# CREMA.net
KiCad netlist of a schematic drawn in EAGLE
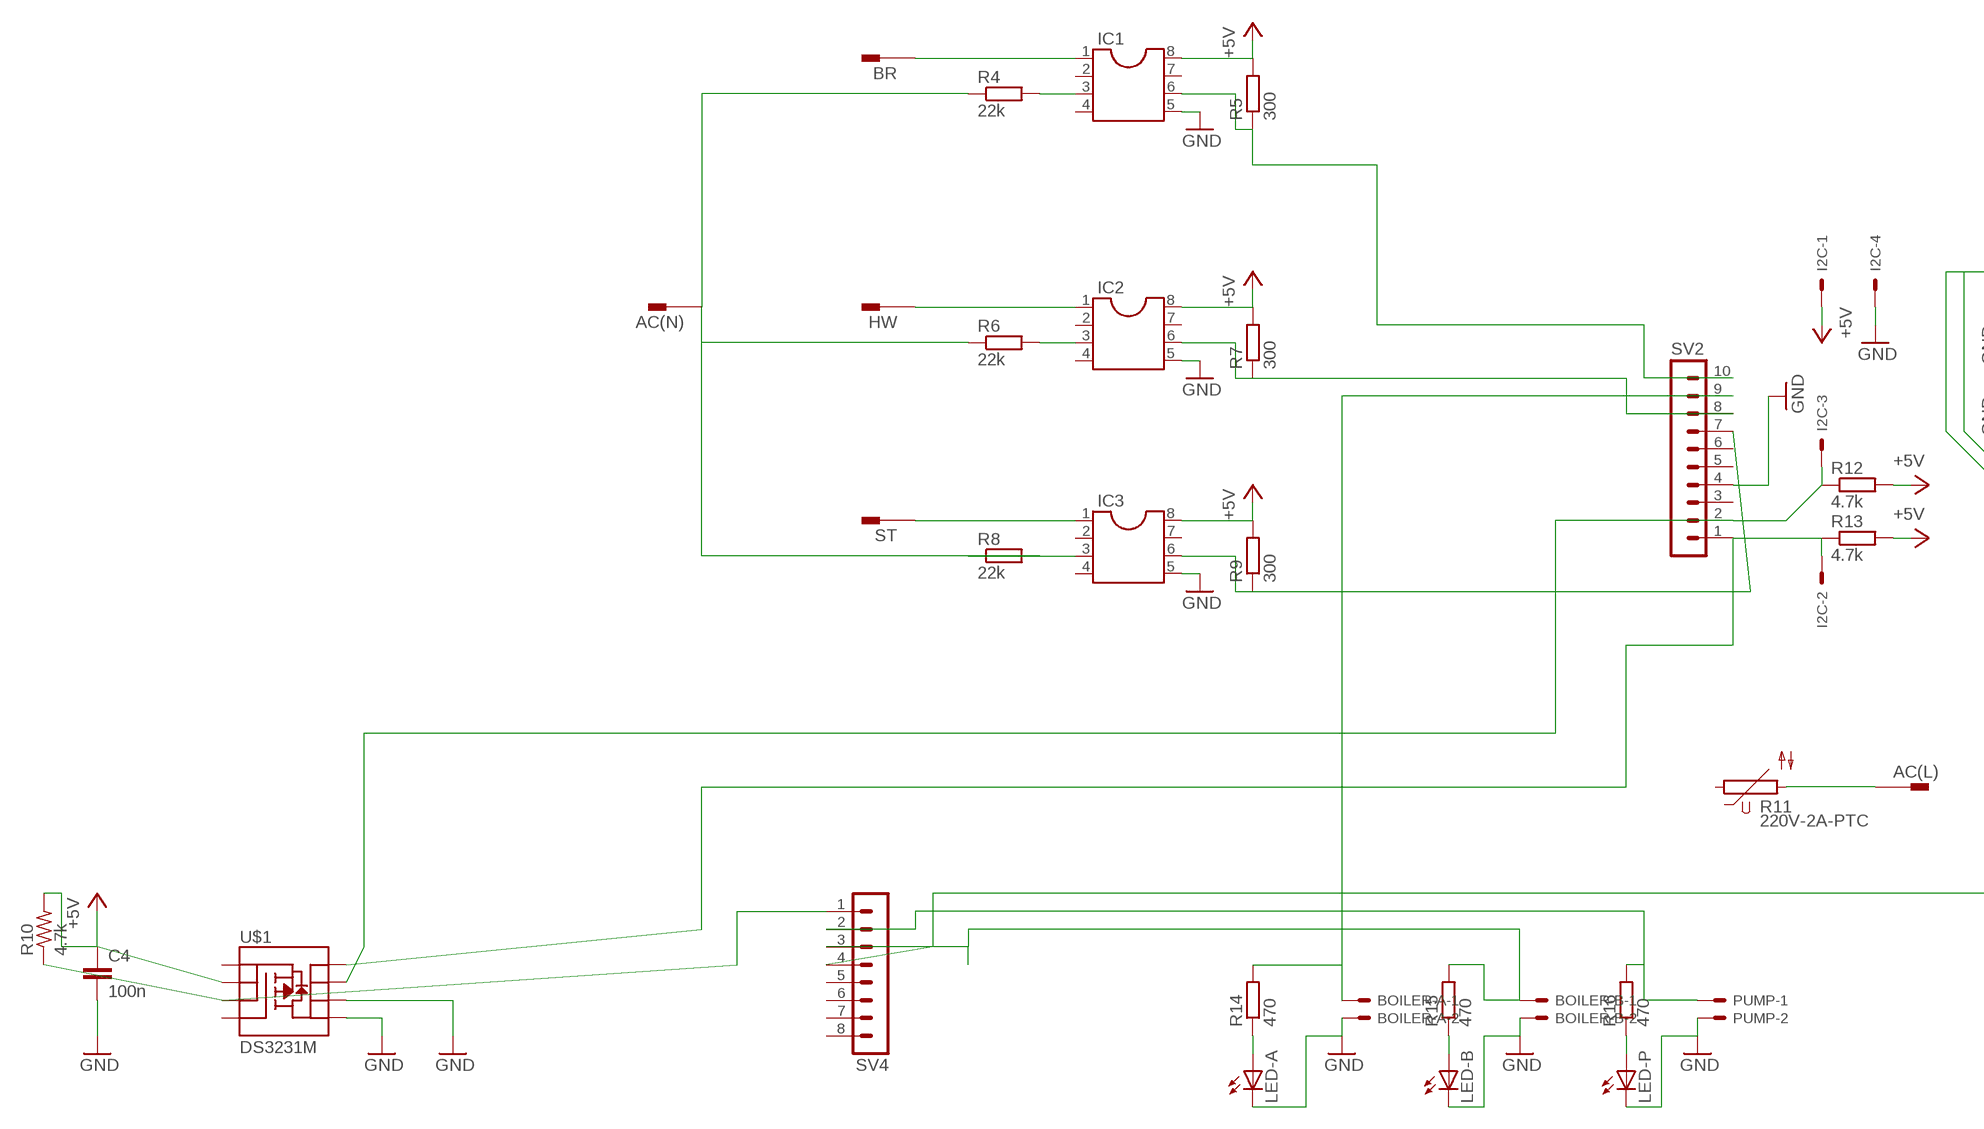
[diagram p0: schematic, sheet 1, part 1 of 2]
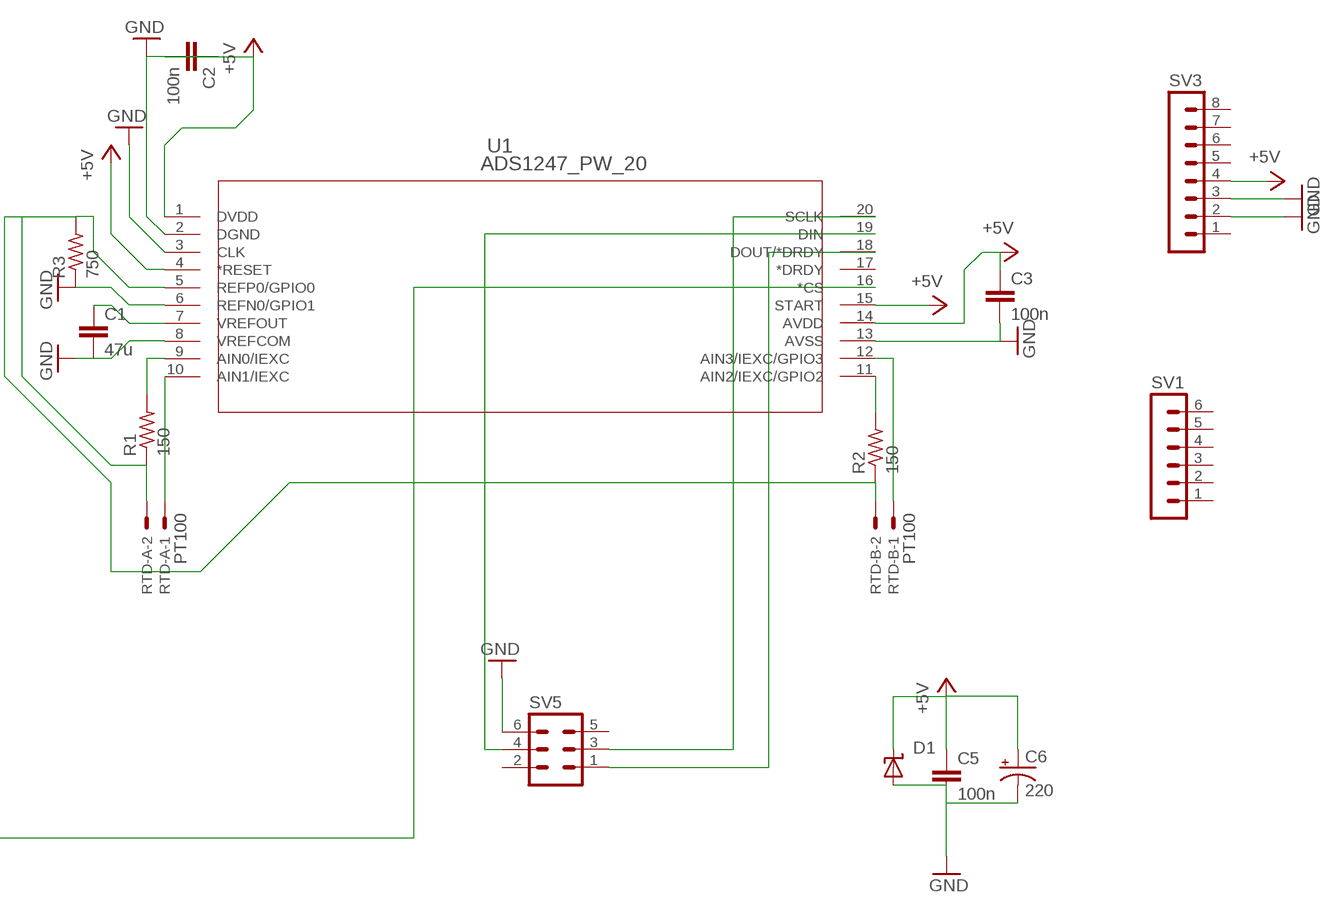
[diagram p1: schematic, sheet 1, part 2 of 2]

(export (version "E")
  (design (tool "Eeschema 10.0.6"))
  (components
    (comp (ref "AC(L)")
      (value "PIN262409-1")
      (footprint "eagle-import:62409-1")
      (libsource (lib "eagle-import") (part "PIN262409-1"))
    )
    (comp (ref "AC(N)")
      (value "PIN262409-1")
      (footprint "eagle-import:62409-1")
      (libsource (lib "eagle-import") (part "PIN262409-1"))
    )
    (comp (ref "BOILER-A")
      (value "C-GRID-02-70543")
      (footprint "eagle-import:70543-02")
      (libsource (lib "eagle-import") (part "C-GRID-02-70543"))
    )
    (comp (ref "BOILER-B")
      (value "C-GRID-02-70543")
      (footprint "eagle-import:70543-02")
      (libsource (lib "eagle-import") (part "C-GRID-02-70543"))
    )
    (comp (ref "BR")
      (value "PIN262409-1")
      (footprint "eagle-import:62409-1")
      (libsource (lib "eagle-import") (part "PIN262409-1"))
    )
    (comp (ref "C1")
      (value "47u")
      (footprint "eagle-import:C0805")
      (libsource (lib "eagle-import") (part "C-EUC0805"))
    )
    (comp (ref "C2")
      (value "100n")
      (footprint "eagle-import:C0805")
      (libsource (lib "eagle-import") (part "C-EUC0805"))
    )
    (comp (ref "C3")
      (value "100n")
      (footprint "eagle-import:C0805")
      (libsource (lib "eagle-import") (part "C-EUC0805"))
    )
    (comp (ref "C4")
      (value "100n")
      (footprint "eagle-import:C0805")
      (libsource (lib "eagle-import") (part "C-EUC0805"))
    )
    (comp (ref "C5")
      (value "100n")
      (footprint "eagle-import:C0805")
      (libsource (lib "eagle-import") (part "C-EUC0805"))
    )
    (comp (ref "C6")
      (value "220")
      (footprint "eagle-import:D_7343-31W")
      (libsource (lib "eagle-import") (part "CPOL-USD/7343-31W"))
    )
    (comp (ref "D1")
      (value "SUPPRESSOR-SMBJ")
      (footprint "eagle-import:SMBJ")
      (libsource (lib "eagle-import") (part "SUPPRESSOR-SMBJ"))
    )
    (comp (ref "HW")
      (value "PIN262409-1")
      (footprint "eagle-import:62409-1")
      (libsource (lib "eagle-import") (part "PIN262409-1"))
    )
    (comp (ref "I2C")
      (value "C-GRID-04-70543")
      (footprint "eagle-import:70543-04")
      (libsource (lib "eagle-import") (part "C-GRID-04-70543"))
    )
    (comp (ref "IC1")
      (value "DIL8")
      (footprint "eagle-import:DIL08")
      (libsource (lib "eagle-import") (part "DIL8"))
    )
    (comp (ref "IC2")
      (value "DIL8")
      (footprint "eagle-import:DIL08")
      (libsource (lib "eagle-import") (part "DIL8"))
    )
    (comp (ref "IC3")
      (value "DIL8")
      (footprint "eagle-import:DIL08")
      (libsource (lib "eagle-import") (part "DIL8"))
    )
    (comp (ref "LED-A")
      (value "LEDSML0603")
      (footprint "eagle-import:SML0603")
      (libsource (lib "eagle-import") (part "LEDSML0603"))
    )
    (comp (ref "LED-B")
      (value "LEDSML0603")
      (footprint "eagle-import:SML0603")
      (libsource (lib "eagle-import") (part "LEDSML0603"))
    )
    (comp (ref "LED-P")
      (value "LEDSML0603")
      (footprint "eagle-import:SML0603")
      (libsource (lib "eagle-import") (part "LEDSML0603"))
    )
    (comp (ref "PUMP")
      (value "C-GRID-02-70543")
      (footprint "eagle-import:70543-02")
      (libsource (lib "eagle-import") (part "C-GRID-02-70543"))
    )
    (comp (ref "R1")
      (value "150")
      (footprint "eagle-import:R0603")
      (libsource (lib "eagle-import") (part "R-US_R0603"))
    )
    (comp (ref "R2")
      (value "150")
      (footprint "eagle-import:R0603")
      (libsource (lib "eagle-import") (part "R-US_R0603"))
    )
    (comp (ref "R3")
      (value "750")
      (footprint "eagle-import:R0603")
      (libsource (lib "eagle-import") (part "R-US_R0603"))
    )
    (comp (ref "R4")
      (value "22k")
      (footprint "eagle-import:R1206")
      (libsource (lib "eagle-import") (part "R-EU_R1206"))
    )
    (comp (ref "R5")
      (value "300")
      (footprint "eagle-import:R1206")
      (libsource (lib "eagle-import") (part "R-EU_R1206"))
    )
    (comp (ref "R6")
      (value "22k")
      (footprint "eagle-import:R1206")
      (libsource (lib "eagle-import") (part "R-EU_R1206"))
    )
    (comp (ref "R7")
      (value "300")
      (footprint "eagle-import:R1206")
      (libsource (lib "eagle-import") (part "R-EU_R1206"))
    )
    (comp (ref "R8")
      (value "22k")
      (footprint "eagle-import:R1206")
      (libsource (lib "eagle-import") (part "R-EU_R1206"))
    )
    (comp (ref "R9")
      (value "300")
      (footprint "eagle-import:R1206")
      (libsource (lib "eagle-import") (part "R-EU_R1206"))
    )
    (comp (ref "R10")
      (value "4.7k")
      (footprint "eagle-import:R0603")
      (libsource (lib "eagle-import") (part "resistor_R-US_R0603"))
    )
    (comp (ref "R11")
      (value "220V-2A-PTC")
      (footprint "eagle-import:S20K11")
      (libsource (lib "eagle-import") (part "S20K11"))
    )
    (comp (ref "R12")
      (value "4.7k")
      (footprint "eagle-import:R0603")
      (libsource (lib "eagle-import") (part "R-EU_R0603"))
    )
    (comp (ref "R13")
      (value "4.7k")
      (footprint "eagle-import:R0603")
      (libsource (lib "eagle-import") (part "R-EU_R0603"))
    )
    (comp (ref "R14")
      (value "470")
      (footprint "eagle-import:R0603")
      (libsource (lib "eagle-import") (part "R-EU_R0603"))
    )
    (comp (ref "R15")
      (value "470")
      (footprint "eagle-import:R0603")
      (libsource (lib "eagle-import") (part "R-EU_R0603"))
    )
    (comp (ref "R16")
      (value "470")
      (footprint "eagle-import:R0603")
      (libsource (lib "eagle-import") (part "R-EU_R0603"))
    )
    (comp (ref "RTD-A")
      (value "PT100")
      (footprint "eagle-import:70543-02")
      (libsource (lib "eagle-import") (part "C-GRID-02-70543"))
    )
    (comp (ref "RTD-B")
      (value "PT100")
      (footprint "eagle-import:70543-02")
      (libsource (lib "eagle-import") (part "C-GRID-02-70543"))
    )
    (comp (ref "ST")
      (value "PIN262409-1")
      (footprint "eagle-import:62409-1")
      (libsource (lib "eagle-import") (part "PIN262409-1"))
    )
    (comp (ref "SV1")
      (value "MA06-1")
      (footprint "eagle-import:MA06-1")
      (libsource (lib "eagle-import") (part "MA06-1"))
    )
    (comp (ref "SV2")
      (value "MA10-1")
      (footprint "eagle-import:MA10-1")
      (libsource (lib "eagle-import") (part "MA10-1"))
    )
    (comp (ref "SV3")
      (value "MA08-1")
      (footprint "eagle-import:MA08-1")
      (libsource (lib "eagle-import") (part "MA08-1"))
    )
    (comp (ref "SV4")
      (value "MA08-1")
      (footprint "eagle-import:MA08-1")
      (libsource (lib "eagle-import") (part "MA08-1"))
    )
    (comp (ref "SV5")
      (value "MA03-2")
      (footprint "eagle-import:MA03-2")
      (libsource (lib "eagle-import") (part "MA03-2"))
    )
    (comp (ref "U$1")
      (value "DS3231M")
      (footprint "eagle-import:SO08")
      (libsource (lib "eagle-import") (part "MOSFET-PCHANNEL-SOIC8SOIC8"))
    )
    (comp (ref "U1")
      (value "ADS1247_PW_20")
      (footprint "eagle-import:PW20")
      (fields
        (field (name "GENERIC_PART_NUMBER") "ADS1247")
        (field (name "MANUFACTURER") "Texas Instruments")
      )
      (libsource (lib "eagle-import") (part "ADS1247_PW_20"))
    )
  )
  (nets
    (net (code "1") (name "+5V") (class "Default")
      (node (ref "C2") (pin "2") (pinfunction "2_2") (pintype "passive"))
      (node (ref "C3") (pin "1") (pinfunction "1_1") (pintype "passive"))
      (node (ref "C4") (pin "1") (pinfunction "1_1") (pintype "passive"))
      (node (ref "C5") (pin "1") (pinfunction "1_1") (pintype "passive"))
      (node (ref "C6") (pin "+") (pinfunction "+_+") (pintype "passive"))
      (node (ref "D1") (pin "C") (pinfunction "C_C") (pintype "passive"))
      (node (ref "I2C") (pin "1") (pinfunction "S_1") (pintype "passive"))
      (node (ref "IC1") (pin "8") (pinfunction "8_8") (pintype "passive"))
      (node (ref "IC2") (pin "8") (pinfunction "8_8") (pintype "passive"))
      (node (ref "IC3") (pin "8") (pinfunction "8_8") (pintype "passive"))
      (node (ref "R10") (pin "2") (pinfunction "2_2") (pintype "passive"))
      (node (ref "R12") (pin "2") (pinfunction "2_2") (pintype "passive"))
      (node (ref "R13") (pin "2") (pinfunction "2_2") (pintype "passive"))
      (node (ref "R5") (pin "2") (pinfunction "2_2") (pintype "passive"))
      (node (ref "R7") (pin "2") (pinfunction "2_2") (pintype "passive"))
      (node (ref "R9") (pin "2") (pinfunction "2_2") (pintype "passive"))
      (node (ref "SV3") (pin "4") (pinfunction "4_4") (pintype "passive"))
      (node (ref "U$1") (pin "2") (pinfunction "S_2") (pintype "bidirectional"))
      (node (ref "U1") (pin "1") (pinfunction "DVDD_1") (pintype "power_in"))
      (node (ref "U1") (pin "14") (pinfunction "AVDD_14") (pintype "power_in"))
      (node (ref "U1") (pin "15") (pinfunction "START_15") (pintype "input"))
      (node (ref "U1") (pin "4") (pinfunction "*RESET_4") (pintype "input"))
    )
    (net (code "2") (name "GND") (class "Default")
      (node (ref "BOILER-A") (pin "2") (pinfunction "S_2") (pintype "passive"))
      (node (ref "BOILER-B") (pin "2") (pinfunction "S_2") (pintype "passive"))
      (node (ref "C1") (pin "2") (pinfunction "2_2") (pintype "passive"))
      (node (ref "C2") (pin "1") (pinfunction "1_1") (pintype "passive"))
      (node (ref "C3") (pin "2") (pinfunction "2_2") (pintype "passive"))
      (node (ref "C4") (pin "2") (pinfunction "2_2") (pintype "passive"))
      (node (ref "C5") (pin "2") (pinfunction "2_2") (pintype "passive"))
      (node (ref "C6") (pin "-") (pinfunction "-_-") (pintype "passive"))
      (node (ref "D1") (pin "A") (pinfunction "A_A") (pintype "passive"))
      (node (ref "I2C") (pin "4") (pinfunction "S_4") (pintype "passive"))
      (node (ref "IC1") (pin "5") (pinfunction "5_5") (pintype "passive"))
      (node (ref "IC2") (pin "5") (pinfunction "5_5") (pintype "passive"))
      (node (ref "IC3") (pin "5") (pinfunction "5_5") (pintype "passive"))
      (node (ref "LED-A") (pin "C") (pinfunction "C_C") (pintype "passive"))
      (node (ref "LED-B") (pin "C") (pinfunction "C_C") (pintype "passive"))
      (node (ref "LED-P") (pin "C") (pinfunction "C_C") (pintype "passive"))
      (node (ref "PUMP") (pin "2") (pinfunction "S_2") (pintype "passive"))
      (node (ref "R3") (pin "1") (pinfunction "1_1") (pintype "passive"))
      (node (ref "SV2") (pin "4") (pinfunction "4_4") (pintype "passive"))
      (node (ref "SV3") (pin "2") (pinfunction "2_2") (pintype "passive"))
      (node (ref "SV3") (pin "3") (pinfunction "3_3") (pintype "passive"))
      (node (ref "SV5") (pin "6") (pinfunction "6_6") (pintype "passive"))
      (node (ref "U$1") (pin "5") (pinfunction "D_5") (pintype "bidirectional"))
      (node (ref "U$1") (pin "6") (pinfunction "D_6") (pintype "bidirectional"))
      (node (ref "U1") (pin "13") (pinfunction "AVSS_13") (pintype "power_in"))
      (node (ref "U1") (pin "2") (pinfunction "DGND_2") (pintype "power_in"))
      (node (ref "U1") (pin "3") (pinfunction "CLK_3") (pintype "input"))
      (node (ref "U1") (pin "6") (pinfunction "REFN0/GPIO1_6") (pintype "bidirectional"))
      (node (ref "U1") (pin "8") (pinfunction "VREFCOM_8") (pintype "output"))
    )
    (net (code "3") (name "Net-(AC(L)-1-PadA1)") (class "Default")
      (node (ref "AC(L)") (pin "A1") (pinfunction "1_A1") (pintype "passive"))
      (node (ref "AC(L)") (pin "A2") (pinfunction "1_A2") (pintype "passive"))
      (node (ref "R11") (pin "2") (pinfunction "2_2") (pintype "passive"))
    )
    (net (code "4") (name "Net-(AC(N)-1-PadA1)") (class "Default")
      (node (ref "AC(N)") (pin "A1") (pinfunction "1_A1") (pintype "passive"))
      (node (ref "AC(N)") (pin "A2") (pinfunction "1_A2") (pintype "passive"))
      (node (ref "R4") (pin "1") (pinfunction "1_1") (pintype "passive"))
      (node (ref "R6") (pin "1") (pinfunction "1_1") (pintype "passive"))
      (node (ref "R8") (pin "2") (pinfunction "2_2") (pintype "passive"))
    )
    (net (code "5") (name "Net-(BOILER-AA-S)") (class "Default")
      (node (ref "BOILER-A") (pin "1") (pinfunction "S_1") (pintype "passive"))
      (node (ref "R14") (pin "2") (pinfunction "2_2") (pintype "passive"))
      (node (ref "SV2") (pin "9") (pinfunction "9_9") (pintype "passive"))
    )
    (net (code "6") (name "Net-(BOILER-BA-S)") (class "Default")
      (node (ref "BOILER-B") (pin "1") (pinfunction "S_1") (pintype "passive"))
      (node (ref "R15") (pin "2") (pinfunction "2_2") (pintype "passive"))
      (node (ref "SV4") (pin "3") (pinfunction "3_3") (pintype "passive"))
    )
    (net (code "7") (name "Net-(BR-1-PadA1)") (class "Default")
      (node (ref "BR") (pin "A1") (pinfunction "1_A1") (pintype "passive"))
      (node (ref "BR") (pin "A2") (pinfunction "1_A2") (pintype "passive"))
      (node (ref "IC1") (pin "1") (pinfunction "1_1") (pintype "passive"))
    )
    (net (code "8") (name "Net-(HW-1-PadA1)") (class "Default")
      (node (ref "HW") (pin "A1") (pinfunction "1_A1") (pintype "passive"))
      (node (ref "HW") (pin "A2") (pinfunction "1_A2") (pintype "passive"))
      (node (ref "IC2") (pin "1") (pinfunction "1_1") (pintype "passive"))
    )
    (net (code "9") (name "Net-(I2CB-S)") (class "Default")
      (node (ref "I2C") (pin "2") (pinfunction "S_2") (pintype "passive"))
      (node (ref "R13") (pin "1") (pinfunction "1_1") (pintype "passive"))
      (node (ref "SV2") (pin "1") (pinfunction "1_1") (pintype "passive"))
      (node (ref "U$1") (pin "8") (pinfunction "D_8") (pintype "bidirectional"))
    )
    (net (code "10") (name "Net-(I2CC-S)") (class "Default")
      (node (ref "I2C") (pin "3") (pinfunction "S_3") (pintype "passive"))
      (node (ref "R12") (pin "1") (pinfunction "1_1") (pintype "passive"))
      (node (ref "SV2") (pin "2") (pinfunction "2_2") (pintype "passive"))
      (node (ref "U$1") (pin "7") (pinfunction "D_7") (pintype "bidirectional"))
    )
    (net (code "11") (name "Net-(IC1-Pad3)") (class "Default")
      (node (ref "IC1") (pin "3") (pinfunction "3_3") (pintype "passive"))
      (node (ref "R4") (pin "2") (pinfunction "2_2") (pintype "passive"))
    )
    (net (code "12") (name "Net-(IC1-Pad6)") (class "Default")
      (node (ref "IC1") (pin "6") (pinfunction "6_6") (pintype "passive"))
      (node (ref "R5") (pin "1") (pinfunction "1_1") (pintype "passive"))
      (node (ref "SV2") (pin "10") (pinfunction "10_10") (pintype "passive"))
    )
    (net (code "13") (name "Net-(IC2-Pad3)") (class "Default")
      (node (ref "IC2") (pin "3") (pinfunction "3_3") (pintype "passive"))
      (node (ref "R6") (pin "2") (pinfunction "2_2") (pintype "passive"))
    )
    (net (code "14") (name "Net-(IC2-Pad6)") (class "Default")
      (node (ref "IC2") (pin "6") (pinfunction "6_6") (pintype "passive"))
      (node (ref "R7") (pin "1") (pinfunction "1_1") (pintype "passive"))
      (node (ref "SV2") (pin "8") (pinfunction "8_8") (pintype "passive"))
    )
    (net (code "15") (name "Net-(IC3-Pad1)") (class "Default")
      (node (ref "IC3") (pin "1") (pinfunction "1_1") (pintype "passive"))
      (node (ref "ST") (pin "A1") (pinfunction "1_A1") (pintype "passive"))
      (node (ref "ST") (pin "A2") (pinfunction "1_A2") (pintype "passive"))
    )
    (net (code "16") (name "Net-(IC3-Pad3)") (class "Default")
      (node (ref "IC3") (pin "3") (pinfunction "3_3") (pintype "passive"))
      (node (ref "R8") (pin "1") (pinfunction "1_1") (pintype "passive"))
    )
    (net (code "17") (name "Net-(IC3-Pad6)") (class "Default")
      (node (ref "IC3") (pin "6") (pinfunction "6_6") (pintype "passive"))
      (node (ref "R9") (pin "1") (pinfunction "1_1") (pintype "passive"))
      (node (ref "SV2") (pin "7") (pinfunction "7_7") (pintype "passive"))
    )
    (net (code "18") (name "Net-(LED-A-PadA)") (class "Default")
      (node (ref "LED-A") (pin "A") (pinfunction "A_A") (pintype "passive"))
      (node (ref "R14") (pin "1") (pinfunction "1_1") (pintype "passive"))
    )
    (net (code "19") (name "Net-(LED-B-PadA)") (class "Default")
      (node (ref "LED-B") (pin "A") (pinfunction "A_A") (pintype "passive"))
      (node (ref "R15") (pin "1") (pinfunction "1_1") (pintype "passive"))
    )
    (net (code "20") (name "Net-(LED-P-PadA)") (class "Default")
      (node (ref "LED-P") (pin "A") (pinfunction "A_A") (pintype "passive"))
      (node (ref "R16") (pin "1") (pinfunction "1_1") (pintype "passive"))
    )
    (net (code "21") (name "Net-(PUMPA-S)") (class "Default")
      (node (ref "PUMP") (pin "1") (pinfunction "S_1") (pintype "passive"))
      (node (ref "R16") (pin "2") (pinfunction "2_2") (pintype "passive"))
      (node (ref "SV4") (pin "2") (pinfunction "2_2") (pintype "passive"))
    )
    (net (code "22") (name "Net-(R10-Pad1)") (class "Default")
      (node (ref "R10") (pin "1") (pinfunction "1_1") (pintype "passive"))
      (node (ref "SV4") (pin "1") (pinfunction "1_1") (pintype "passive"))
      (node (ref "U$1") (pin "3") (pinfunction "S_3") (pintype "bidirectional"))
    )
    (net (code "23") (name "Net-(RTD-AA-S)") (class "Default")
      (node (ref "RTD-A") (pin "1") (pinfunction "S_1") (pintype "passive"))
      (node (ref "U1") (pin "10") (pinfunction "AIN1/IEXC_10") (pintype "input"))
    )
    (net (code "24") (name "Net-(RTD-AB-S)") (class "Default")
      (node (ref "R1") (pin "1") (pinfunction "1_1") (pintype "passive"))
      (node (ref "R2") (pin "1") (pinfunction "1_1") (pintype "passive"))
      (node (ref "R3") (pin "2") (pinfunction "2_2") (pintype "passive"))
      (node (ref "RTD-A") (pin "2") (pinfunction "S_2") (pintype "passive"))
      (node (ref "RTD-B") (pin "2") (pinfunction "S_2") (pintype "passive"))
      (node (ref "U1") (pin "5") (pinfunction "REFP0/GPIO0_5") (pintype "bidirectional"))
    )
    (net (code "25") (name "Net-(RTD-BA-S)") (class "Default")
      (node (ref "RTD-B") (pin "1") (pinfunction "S_1") (pintype "passive"))
      (node (ref "U1") (pin "12") (pinfunction "AIN3/IEXC/GPIO3_12") (pintype "bidirectional"))
    )
    (net (code "26") (name "Net-(U1-*CS)") (class "Default")
      (node (ref "SV4") (pin "4") (pinfunction "4_4") (pintype "passive"))
      (node (ref "U1") (pin "16") (pinfunction "*CS_16") (pintype "input"))
    )
    (net (code "27") (name "Net-(U1-AIN0{slash}IEXC)") (class "Default")
      (node (ref "R1") (pin "2") (pinfunction "2_2") (pintype "passive"))
      (node (ref "U1") (pin "9") (pinfunction "AIN0/IEXC_9") (pintype "input"))
    )
    (net (code "28") (name "Net-(U1-AIN2{slash}IEXC{slash}GPIO2)") (class "Default")
      (node (ref "R2") (pin "2") (pinfunction "2_2") (pintype "passive"))
      (node (ref "U1") (pin "11") (pinfunction "AIN2/IEXC/GPIO2_11") (pintype "bidirectional"))
    )
    (net (code "29") (name "Net-(U1-DIN)") (class "Default")
      (node (ref "SV5") (pin "4") (pinfunction "4_4") (pintype "passive"))
      (node (ref "U1") (pin "19") (pinfunction "DIN_19") (pintype "input"))
    )
    (net (code "30") (name "Net-(U1-DOUT{slash}*DRDY)") (class "Default")
      (node (ref "SV5") (pin "1") (pinfunction "1_1") (pintype "passive"))
      (node (ref "U1") (pin "18") (pinfunction "DOUT/*DRDY_18") (pintype "output"))
    )
    (net (code "31") (name "Net-(U1-SCLK)") (class "Default")
      (node (ref "SV5") (pin "3") (pinfunction "3_3") (pintype "passive"))
      (node (ref "U1") (pin "20") (pinfunction "SCLK_20") (pintype "input"))
    )
    (net (code "32") (name "Net-(U1-VREFOUT)") (class "Default")
      (node (ref "C1") (pin "1") (pinfunction "1_1") (pintype "passive"))
      (node (ref "U1") (pin "7") (pinfunction "VREFOUT_7") (pintype "output"))
    )
    (net (code "33") (name "unconnected-(IC1-Pad2)") (class "Default")
      (node (ref "IC1") (pin "2") (pinfunction "2_2") (pintype "passive"))
    )
    (net (code "34") (name "unconnected-(IC1-Pad4)") (class "Default")
      (node (ref "IC1") (pin "4") (pinfunction "4_4") (pintype "passive"))
    )
    (net (code "35") (name "unconnected-(IC1-Pad7)") (class "Default")
      (node (ref "IC1") (pin "7") (pinfunction "7_7") (pintype "passive"))
    )
    (net (code "36") (name "unconnected-(IC2-Pad2)") (class "Default")
      (node (ref "IC2") (pin "2") (pinfunction "2_2") (pintype "passive"))
    )
    (net (code "37") (name "unconnected-(IC2-Pad4)") (class "Default")
      (node (ref "IC2") (pin "4") (pinfunction "4_4") (pintype "passive"))
    )
    (net (code "38") (name "unconnected-(IC2-Pad7)") (class "Default")
      (node (ref "IC2") (pin "7") (pinfunction "7_7") (pintype "passive"))
    )
    (net (code "39") (name "unconnected-(IC3-Pad2)") (class "Default")
      (node (ref "IC3") (pin "2") (pinfunction "2_2") (pintype "passive"))
    )
    (net (code "40") (name "unconnected-(IC3-Pad4)") (class "Default")
      (node (ref "IC3") (pin "4") (pinfunction "4_4") (pintype "passive"))
    )
    (net (code "41") (name "unconnected-(IC3-Pad7)") (class "Default")
      (node (ref "IC3") (pin "7") (pinfunction "7_7") (pintype "passive"))
    )
    (net (code "42") (name "unconnected-(R11-Pad1)") (class "Default")
      (node (ref "R11") (pin "1") (pinfunction "1_1") (pintype "passive"))
    )
    (net (code "43") (name "unconnected-(SV1-Pad1)") (class "Default")
      (node (ref "SV1") (pin "1") (pinfunction "1_1") (pintype "passive"))
    )
    (net (code "44") (name "unconnected-(SV1-Pad2)") (class "Default")
      (node (ref "SV1") (pin "2") (pinfunction "2_2") (pintype "passive"))
    )
    (net (code "45") (name "unconnected-(SV1-Pad3)") (class "Default")
      (node (ref "SV1") (pin "3") (pinfunction "3_3") (pintype "passive"))
    )
    (net (code "46") (name "unconnected-(SV1-Pad4)") (class "Default")
      (node (ref "SV1") (pin "4") (pinfunction "4_4") (pintype "passive"))
    )
    (net (code "47") (name "unconnected-(SV1-Pad5)") (class "Default")
      (node (ref "SV1") (pin "5") (pinfunction "5_5") (pintype "passive"))
    )
    (net (code "48") (name "unconnected-(SV1-Pad6)") (class "Default")
      (node (ref "SV1") (pin "6") (pinfunction "6_6") (pintype "passive"))
    )
    (net (code "49") (name "unconnected-(SV2-Pad3)") (class "Default")
      (node (ref "SV2") (pin "3") (pinfunction "3_3") (pintype "passive"))
    )
    (net (code "50") (name "unconnected-(SV2-Pad5)") (class "Default")
      (node (ref "SV2") (pin "5") (pinfunction "5_5") (pintype "passive"))
    )
    (net (code "51") (name "unconnected-(SV2-Pad6)") (class "Default")
      (node (ref "SV2") (pin "6") (pinfunction "6_6") (pintype "passive"))
    )
    (net (code "52") (name "unconnected-(SV3-Pad1)") (class "Default")
      (node (ref "SV3") (pin "1") (pinfunction "1_1") (pintype "passive"))
    )
    (net (code "53") (name "unconnected-(SV3-Pad5)") (class "Default")
      (node (ref "SV3") (pin "5") (pinfunction "5_5") (pintype "passive"))
    )
    (net (code "54") (name "unconnected-(SV3-Pad6)") (class "Default")
      (node (ref "SV3") (pin "6") (pinfunction "6_6") (pintype "passive"))
    )
    (net (code "55") (name "unconnected-(SV3-Pad7)") (class "Default")
      (node (ref "SV3") (pin "7") (pinfunction "7_7") (pintype "passive"))
    )
    (net (code "56") (name "unconnected-(SV3-Pad8)") (class "Default")
      (node (ref "SV3") (pin "8") (pinfunction "8_8") (pintype "passive"))
    )
    (net (code "57") (name "unconnected-(SV4-Pad5)") (class "Default")
      (node (ref "SV4") (pin "5") (pinfunction "5_5") (pintype "passive"))
    )
    (net (code "58") (name "unconnected-(SV4-Pad6)") (class "Default")
      (node (ref "SV4") (pin "6") (pinfunction "6_6") (pintype "passive"))
    )
    (net (code "59") (name "unconnected-(SV4-Pad7)") (class "Default")
      (node (ref "SV4") (pin "7") (pinfunction "7_7") (pintype "passive"))
    )
    (net (code "60") (name "unconnected-(SV4-Pad8)") (class "Default")
      (node (ref "SV4") (pin "8") (pinfunction "8_8") (pintype "passive"))
    )
    (net (code "61") (name "unconnected-(SV5-Pad2)") (class "Default")
      (node (ref "SV5") (pin "2") (pinfunction "2_2") (pintype "passive"))
    )
    (net (code "62") (name "unconnected-(SV5-Pad5)") (class "Default")
      (node (ref "SV5") (pin "5") (pinfunction "5_5") (pintype "passive"))
    )
    (net (code "63") (name "unconnected-(U$1-G-Pad4)") (class "Default")
      (node (ref "U$1") (pin "4") (pinfunction "G_4") (pintype "bidirectional"))
    )
    (net (code "64") (name "unconnected-(U$1-S-Pad1)") (class "Default")
      (node (ref "U$1") (pin "1") (pinfunction "S_1") (pintype "bidirectional"))
    )
    (net (code "65") (name "unconnected-(U1-*DRDY-Pad17)") (class "Default")
      (node (ref "U1") (pin "17") (pinfunction "*DRDY_17") (pintype "output"))
    )
  )
)
